# OptoBidirectional.net
KiCad netlist of a schematic drawn in EAGLE
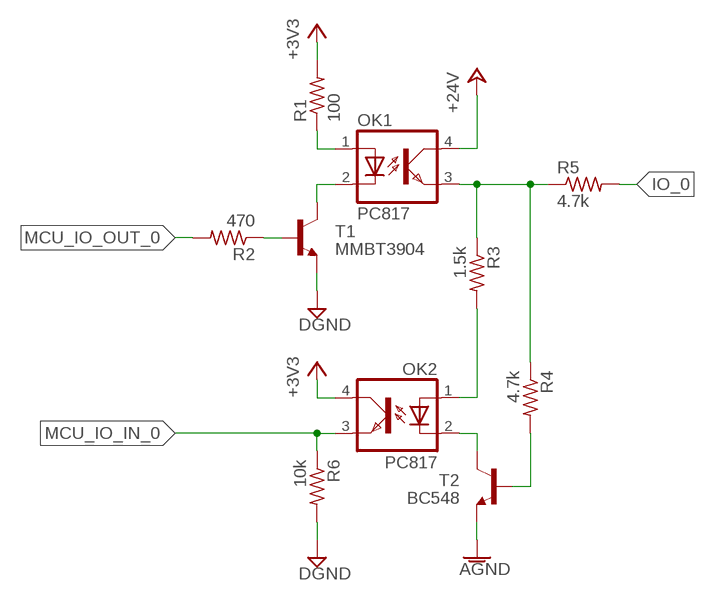
[diagram p0: schematic, sheet 1]

(export (version "E")
  (design (tool "Eeschema 10.0.6"))
  (components
    (comp (ref "OK1")
      (value "PC817")
      (footprint "eagle-import:DIL04")
      (fields (field (name "MPN") "PC817X4J000F"))
      (libsource (lib "eagle-import") (part "PC817"))
    )
    (comp (ref "OK2")
      (value "PC817")
      (footprint "eagle-import:DIL04")
      (fields (field (name "MPN") "PC817X4J000F"))
      (libsource (lib "eagle-import") (part "PC817"))
    )
    (comp (ref "R1")
      (value "100")
      (footprint "eagle-import:0204_7")
      (libsource (lib "eagle-import") (part "R-US_0204/7"))
    )
    (comp (ref "R2")
      (value "470")
      (footprint "eagle-import:R0402")
      (libsource (lib "eagle-import") (part "R-US_R0402"))
    )
    (comp (ref "R3")
      (value "1.5k")
      (footprint "eagle-import:0204_5")
      (libsource (lib "eagle-import") (part "R-US_0204/5"))
    )
    (comp (ref "R4")
      (value "4.7k")
      (footprint "eagle-import:0204V")
      (libsource (lib "eagle-import") (part "R-US_0204/2V"))
    )
    (comp (ref "R5")
      (value "4.7k")
      (footprint "eagle-import:0204V")
      (libsource (lib "eagle-import") (part "R-US_0204/2V"))
    )
    (comp (ref "R6")
      (value "10k")
      (footprint "eagle-import:0204_5")
      (libsource (lib "eagle-import") (part "R-US_0204/5"))
    )
    (comp (ref "T1")
      (value "MMBT3904")
      (footprint "eagle-import:SOT23-BEC")
      (libsource (lib "eagle-import") (part "-NPN-SOT23-BECMMBT3904LT1"))
    )
    (comp (ref "T2")
      (value "BC548")
      (footprint "eagle-import:TO92-CBE")
      (libsource (lib "eagle-import") (part "-NPN-TO92-CBEBC548"))
    )
  )
  (nets
    (net (code "1") (name "+3V3") (class "Default")
      (node (ref "OK2") (pin "4") (pinfunction "COL_4") (pintype "passive"))
      (node (ref "R1") (pin "2") (pinfunction "2_2") (pintype "passive"))
    )
    (net (code "2") (name "+24V") (class "Default")
      (node (ref "OK1") (pin "4") (pinfunction "COL_4") (pintype "passive"))
    )
    (net (code "3") (name "AGND") (class "Default")
      (node (ref "T2") (pin "E") (pinfunction "E_E") (pintype "passive"))
    )
    (net (code "4") (name "DGND") (class "Default")
      (node (ref "R6") (pin "2") (pinfunction "2_2") (pintype "passive"))
      (node (ref "T1") (pin "E") (pinfunction "E_E") (pintype "passive"))
    )
    (net (code "5") (name "IO_0") (class "Default")
      (node (ref "R5") (pin "2") (pinfunction "2_2") (pintype "passive"))
    )
    (net (code "6") (name "MCU_IO_IN_0") (class "Default")
      (node (ref "OK2") (pin "3") (pinfunction "EMIT_3") (pintype "passive"))
      (node (ref "R6") (pin "1") (pinfunction "1_1") (pintype "passive"))
    )
    (net (code "7") (name "MCU_IO_OUT_0") (class "Default")
      (node (ref "R2") (pin "2") (pinfunction "2_2") (pintype "passive"))
    )
    (net (code "8") (name "Net-(OK1-A)") (class "Default")
      (node (ref "OK1") (pin "1") (pinfunction "A_1") (pintype "passive"))
      (node (ref "R1") (pin "1") (pinfunction "1_1") (pintype "passive"))
    )
    (net (code "9") (name "Net-(OK1-C)") (class "Default")
      (node (ref "OK1") (pin "2") (pinfunction "C_2") (pintype "passive"))
      (node (ref "T1") (pin "C") (pinfunction "C_C") (pintype "passive"))
    )
    (net (code "10") (name "Net-(OK1-EMIT)") (class "Default")
      (node (ref "OK1") (pin "3") (pinfunction "EMIT_3") (pintype "passive"))
      (node (ref "R3") (pin "1") (pinfunction "1_1") (pintype "passive"))
      (node (ref "R4") (pin "1") (pinfunction "1_1") (pintype "passive"))
      (node (ref "R5") (pin "1") (pinfunction "1_1") (pintype "passive"))
    )
    (net (code "11") (name "Net-(OK2-A)") (class "Default")
      (node (ref "OK2") (pin "1") (pinfunction "A_1") (pintype "passive"))
      (node (ref "R3") (pin "2") (pinfunction "2_2") (pintype "passive"))
    )
    (net (code "12") (name "Net-(OK2-C)") (class "Default")
      (node (ref "OK2") (pin "2") (pinfunction "C_2") (pintype "passive"))
      (node (ref "T2") (pin "C") (pinfunction "C_C") (pintype "passive"))
    )
    (net (code "13") (name "Net-(R2-Pad1)") (class "Default")
      (node (ref "R2") (pin "1") (pinfunction "1_1") (pintype "passive"))
      (node (ref "T1") (pin "B") (pinfunction "B_B") (pintype "passive"))
    )
    (net (code "14") (name "Net-(R4-Pad2)") (class "Default")
      (node (ref "R4") (pin "2") (pinfunction "2_2") (pintype "passive"))
      (node (ref "T2") (pin "B") (pinfunction "B_B") (pintype "passive"))
    )
  )
)
